# LedExtensionBoard.net
KiCad netlist of a schematic drawn in EAGLE
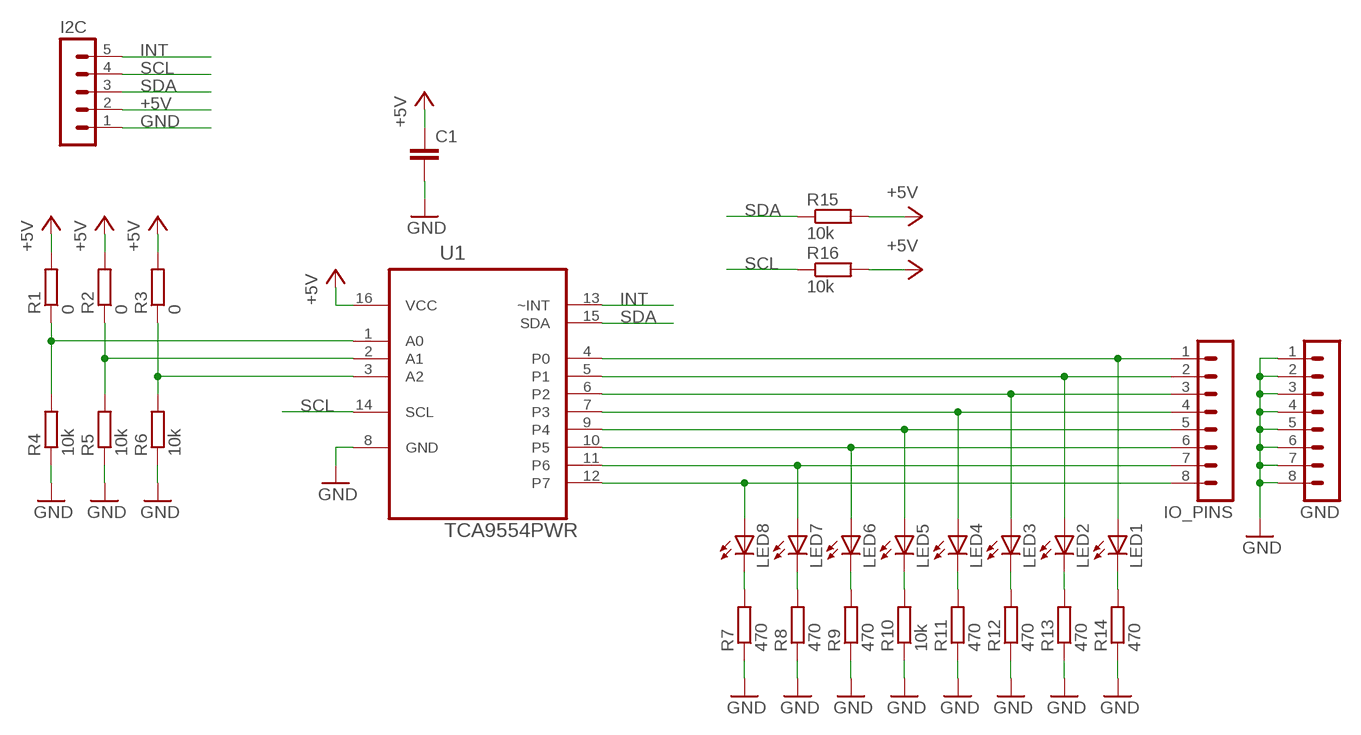
[diagram p0: schematic, sheet 1]

(export (version "E")
  (design (tool "Eeschema 10.0.6"))
  (components
    (comp (ref "C1")
      (value "C-EUC0805")
      (footprint "eagle-import:C0805")
      (libsource (lib "eagle-import") (part "C-EUC0805"))
    )
    (comp (ref "GND")
      (value "MA08-1")
      (footprint "eagle-import:MA08-1")
      (libsource (lib "eagle-import") (part "MA08-1"))
    )
    (comp (ref "I2C")
      (value "MA05-1")
      (footprint "eagle-import:MA05-1")
      (libsource (lib "eagle-import") (part "MA05-1"))
    )
    (comp (ref "IO_PINS")
      (value "MA08-1")
      (footprint "eagle-import:MA08-1")
      (libsource (lib "eagle-import") (part "MA08-1"))
    )
    (comp (ref "LED1")
      (value "LEDSML0805")
      (footprint "eagle-import:SML0805")
      (libsource (lib "eagle-import") (part "LEDSML0805"))
    )
    (comp (ref "LED2")
      (value "LEDSML0805")
      (footprint "eagle-import:SML0805")
      (libsource (lib "eagle-import") (part "LEDSML0805"))
    )
    (comp (ref "LED3")
      (value "LEDSML0805")
      (footprint "eagle-import:SML0805")
      (libsource (lib "eagle-import") (part "LEDSML0805"))
    )
    (comp (ref "LED4")
      (value "LEDSML0805")
      (footprint "eagle-import:SML0805")
      (libsource (lib "eagle-import") (part "LEDSML0805"))
    )
    (comp (ref "LED5")
      (value "LEDSML0805")
      (footprint "eagle-import:SML0805")
      (libsource (lib "eagle-import") (part "LEDSML0805"))
    )
    (comp (ref "LED6")
      (value "LEDSML0805")
      (footprint "eagle-import:SML0805")
      (libsource (lib "eagle-import") (part "LEDSML0805"))
    )
    (comp (ref "LED7")
      (value "LEDSML0805")
      (footprint "eagle-import:SML0805")
      (libsource (lib "eagle-import") (part "LEDSML0805"))
    )
    (comp (ref "LED8")
      (value "LEDSML0805")
      (footprint "eagle-import:SML0805")
      (libsource (lib "eagle-import") (part "LEDSML0805"))
    )
    (comp (ref "R1")
      (value "0")
      (footprint "eagle-import:M1206")
      (libsource (lib "eagle-import") (part "R-EU_M1206"))
    )
    (comp (ref "R2")
      (value "0")
      (footprint "eagle-import:M1206")
      (libsource (lib "eagle-import") (part "R-EU_M1206"))
    )
    (comp (ref "R3")
      (value "0")
      (footprint "eagle-import:M1206")
      (libsource (lib "eagle-import") (part "R-EU_M1206"))
    )
    (comp (ref "R4")
      (value "10k")
      (footprint "eagle-import:M0805")
      (libsource (lib "eagle-import") (part "R-EU_M0805"))
    )
    (comp (ref "R5")
      (value "10k")
      (footprint "eagle-import:M0805")
      (libsource (lib "eagle-import") (part "R-EU_M0805"))
    )
    (comp (ref "R6")
      (value "10k")
      (footprint "eagle-import:M0805")
      (libsource (lib "eagle-import") (part "R-EU_M0805"))
    )
    (comp (ref "R7")
      (value "470")
      (footprint "eagle-import:M0805")
      (libsource (lib "eagle-import") (part "R-EU_M0805"))
    )
    (comp (ref "R8")
      (value "470")
      (footprint "eagle-import:M0805")
      (libsource (lib "eagle-import") (part "R-EU_M0805"))
    )
    (comp (ref "R9")
      (value "470")
      (footprint "eagle-import:M0805")
      (libsource (lib "eagle-import") (part "R-EU_M0805"))
    )
    (comp (ref "R10")
      (value "10k")
      (footprint "eagle-import:M0805")
      (libsource (lib "eagle-import") (part "R-EU_M0805"))
    )
    (comp (ref "R11")
      (value "470")
      (footprint "eagle-import:M0805")
      (libsource (lib "eagle-import") (part "R-EU_M0805"))
    )
    (comp (ref "R12")
      (value "470")
      (footprint "eagle-import:M0805")
      (libsource (lib "eagle-import") (part "R-EU_M0805"))
    )
    (comp (ref "R13")
      (value "470")
      (footprint "eagle-import:M0805")
      (libsource (lib "eagle-import") (part "R-EU_M0805"))
    )
    (comp (ref "R14")
      (value "470")
      (footprint "eagle-import:M0805")
      (libsource (lib "eagle-import") (part "R-EU_M0805"))
    )
    (comp (ref "R15")
      (value "10k")
      (footprint "eagle-import:M0805")
      (libsource (lib "eagle-import") (part "R-EU_M0805"))
    )
    (comp (ref "R16")
      (value "10k")
      (footprint "eagle-import:M0805")
      (libsource (lib "eagle-import") (part "R-EU_M0805"))
    )
    (comp (ref "U1")
      (value "TCA9554PWR")
      (footprint "eagle-import:SOP65P640X120-16N")
      (fields (field (name "MF") "Texas Instruments"))
      (libsource (lib "eagle-import") (part "TCA9554PWR"))
    )
  )
  (nets
    (net (code "1") (name "+5V") (class "Default")
      (node (ref "C1") (pin "1") (pinfunction "1_1") (pintype "passive"))
      (node (ref "I2C") (pin "2") (pinfunction "2_2") (pintype "passive"))
      (node (ref "R1") (pin "2") (pinfunction "2_2") (pintype "passive"))
      (node (ref "R15") (pin "2") (pinfunction "2_2") (pintype "passive"))
      (node (ref "R16") (pin "2") (pinfunction "2_2") (pintype "passive"))
      (node (ref "R2") (pin "2") (pinfunction "2_2") (pintype "passive"))
      (node (ref "R3") (pin "2") (pinfunction "2_2") (pintype "passive"))
      (node (ref "U1") (pin "16") (pinfunction "VCC_16") (pintype "power_in"))
    )
    (net (code "2") (name "/INT") (class "Default")
      (node (ref "I2C") (pin "5") (pinfunction "5_5") (pintype "passive"))
      (node (ref "U1") (pin "13") (pinfunction "~{INT}_13") (pintype "output"))
    )
    (net (code "3") (name "/SCL") (class "Default")
      (node (ref "I2C") (pin "4") (pinfunction "4_4") (pintype "passive"))
      (node (ref "R16") (pin "1") (pinfunction "1_1") (pintype "passive"))
      (node (ref "U1") (pin "14") (pinfunction "SCL_14") (pintype "input"))
    )
    (net (code "4") (name "/SDA") (class "Default")
      (node (ref "I2C") (pin "3") (pinfunction "3_3") (pintype "passive"))
      (node (ref "R15") (pin "1") (pinfunction "1_1") (pintype "passive"))
      (node (ref "U1") (pin "15") (pinfunction "SDA_15") (pintype "bidirectional"))
    )
    (net (code "5") (name "GND") (class "Default")
      (node (ref "C1") (pin "2") (pinfunction "2_2") (pintype "passive"))
      (node (ref "GND") (pin "1") (pinfunction "1_1") (pintype "passive"))
      (node (ref "GND") (pin "2") (pinfunction "2_2") (pintype "passive"))
      (node (ref "GND") (pin "3") (pinfunction "3_3") (pintype "passive"))
      (node (ref "GND") (pin "4") (pinfunction "4_4") (pintype "passive"))
      (node (ref "GND") (pin "5") (pinfunction "5_5") (pintype "passive"))
      (node (ref "GND") (pin "6") (pinfunction "6_6") (pintype "passive"))
      (node (ref "GND") (pin "7") (pinfunction "7_7") (pintype "passive"))
      (node (ref "GND") (pin "8") (pinfunction "8_8") (pintype "passive"))
      (node (ref "I2C") (pin "1") (pinfunction "1_1") (pintype "passive"))
      (node (ref "R10") (pin "1") (pinfunction "1_1") (pintype "passive"))
      (node (ref "R11") (pin "1") (pinfunction "1_1") (pintype "passive"))
      (node (ref "R12") (pin "1") (pinfunction "1_1") (pintype "passive"))
      (node (ref "R13") (pin "1") (pinfunction "1_1") (pintype "passive"))
      (node (ref "R14") (pin "1") (pinfunction "1_1") (pintype "passive"))
      (node (ref "R4") (pin "1") (pinfunction "1_1") (pintype "passive"))
      (node (ref "R5") (pin "1") (pinfunction "1_1") (pintype "passive"))
      (node (ref "R6") (pin "1") (pinfunction "1_1") (pintype "passive"))
      (node (ref "R7") (pin "1") (pinfunction "1_1") (pintype "passive"))
      (node (ref "R8") (pin "1") (pinfunction "1_1") (pintype "passive"))
      (node (ref "R9") (pin "1") (pinfunction "1_1") (pintype "passive"))
      (node (ref "U1") (pin "8") (pinfunction "GND_8") (pintype "passive"))
    )
    (net (code "6") (name "Net-(LED1-PadC)") (class "Default")
      (node (ref "LED1") (pin "C") (pinfunction "C_C") (pintype "passive"))
      (node (ref "R14") (pin "2") (pinfunction "2_2") (pintype "passive"))
    )
    (net (code "7") (name "Net-(LED2-PadC)") (class "Default")
      (node (ref "LED2") (pin "C") (pinfunction "C_C") (pintype "passive"))
      (node (ref "R13") (pin "2") (pinfunction "2_2") (pintype "passive"))
    )
    (net (code "8") (name "Net-(LED3-PadC)") (class "Default")
      (node (ref "LED3") (pin "C") (pinfunction "C_C") (pintype "passive"))
      (node (ref "R12") (pin "2") (pinfunction "2_2") (pintype "passive"))
    )
    (net (code "9") (name "Net-(LED4-PadC)") (class "Default")
      (node (ref "LED4") (pin "C") (pinfunction "C_C") (pintype "passive"))
      (node (ref "R11") (pin "2") (pinfunction "2_2") (pintype "passive"))
    )
    (net (code "10") (name "Net-(LED5-PadC)") (class "Default")
      (node (ref "LED5") (pin "C") (pinfunction "C_C") (pintype "passive"))
      (node (ref "R10") (pin "2") (pinfunction "2_2") (pintype "passive"))
    )
    (net (code "11") (name "Net-(LED6-PadC)") (class "Default")
      (node (ref "LED6") (pin "C") (pinfunction "C_C") (pintype "passive"))
      (node (ref "R9") (pin "2") (pinfunction "2_2") (pintype "passive"))
    )
    (net (code "12") (name "Net-(LED7-PadC)") (class "Default")
      (node (ref "LED7") (pin "C") (pinfunction "C_C") (pintype "passive"))
      (node (ref "R8") (pin "2") (pinfunction "2_2") (pintype "passive"))
    )
    (net (code "13") (name "Net-(LED8-PadC)") (class "Default")
      (node (ref "LED8") (pin "C") (pinfunction "C_C") (pintype "passive"))
      (node (ref "R7") (pin "2") (pinfunction "2_2") (pintype "passive"))
    )
    (net (code "14") (name "Net-(U1-A0)") (class "Default")
      (node (ref "R1") (pin "1") (pinfunction "1_1") (pintype "passive"))
      (node (ref "R4") (pin "2") (pinfunction "2_2") (pintype "passive"))
      (node (ref "U1") (pin "1") (pinfunction "A0_1") (pintype "input"))
    )
    (net (code "15") (name "Net-(U1-A1)") (class "Default")
      (node (ref "R2") (pin "1") (pinfunction "1_1") (pintype "passive"))
      (node (ref "R5") (pin "2") (pinfunction "2_2") (pintype "passive"))
      (node (ref "U1") (pin "2") (pinfunction "A1_2") (pintype "input"))
    )
    (net (code "16") (name "Net-(U1-A2)") (class "Default")
      (node (ref "R3") (pin "1") (pinfunction "1_1") (pintype "passive"))
      (node (ref "R6") (pin "2") (pinfunction "2_2") (pintype "passive"))
      (node (ref "U1") (pin "3") (pinfunction "A2_3") (pintype "input"))
    )
    (net (code "17") (name "Net-(U1-P0)") (class "Default")
      (node (ref "IO_PINS") (pin "1") (pinfunction "1_1") (pintype "passive"))
      (node (ref "LED1") (pin "A") (pinfunction "A_A") (pintype "passive"))
      (node (ref "U1") (pin "4") (pinfunction "P0_4") (pintype "bidirectional"))
    )
    (net (code "18") (name "Net-(U1-P1)") (class "Default")
      (node (ref "IO_PINS") (pin "2") (pinfunction "2_2") (pintype "passive"))
      (node (ref "LED2") (pin "A") (pinfunction "A_A") (pintype "passive"))
      (node (ref "U1") (pin "5") (pinfunction "P1_5") (pintype "bidirectional"))
    )
    (net (code "19") (name "Net-(U1-P2)") (class "Default")
      (node (ref "IO_PINS") (pin "3") (pinfunction "3_3") (pintype "passive"))
      (node (ref "LED3") (pin "A") (pinfunction "A_A") (pintype "passive"))
      (node (ref "U1") (pin "6") (pinfunction "P2_6") (pintype "bidirectional"))
    )
    (net (code "20") (name "Net-(U1-P3)") (class "Default")
      (node (ref "IO_PINS") (pin "4") (pinfunction "4_4") (pintype "passive"))
      (node (ref "LED4") (pin "A") (pinfunction "A_A") (pintype "passive"))
      (node (ref "U1") (pin "7") (pinfunction "P3_7") (pintype "bidirectional"))
    )
    (net (code "21") (name "Net-(U1-P4)") (class "Default")
      (node (ref "IO_PINS") (pin "5") (pinfunction "5_5") (pintype "passive"))
      (node (ref "LED5") (pin "A") (pinfunction "A_A") (pintype "passive"))
      (node (ref "U1") (pin "9") (pinfunction "P4_9") (pintype "bidirectional"))
    )
    (net (code "22") (name "Net-(U1-P5)") (class "Default")
      (node (ref "IO_PINS") (pin "6") (pinfunction "6_6") (pintype "passive"))
      (node (ref "LED6") (pin "A") (pinfunction "A_A") (pintype "passive"))
      (node (ref "U1") (pin "10") (pinfunction "P5_10") (pintype "bidirectional"))
    )
    (net (code "23") (name "Net-(U1-P6)") (class "Default")
      (node (ref "IO_PINS") (pin "7") (pinfunction "7_7") (pintype "passive"))
      (node (ref "LED7") (pin "A") (pinfunction "A_A") (pintype "passive"))
      (node (ref "U1") (pin "11") (pinfunction "P6_11") (pintype "bidirectional"))
    )
    (net (code "24") (name "Net-(U1-P7)") (class "Default")
      (node (ref "IO_PINS") (pin "8") (pinfunction "8_8") (pintype "passive"))
      (node (ref "LED8") (pin "A") (pinfunction "A_A") (pintype "passive"))
      (node (ref "U1") (pin "12") (pinfunction "P7_12") (pintype "bidirectional"))
    )
  )
)
